# schema.net
KiCad netlist of a schematic drawn in EAGLE
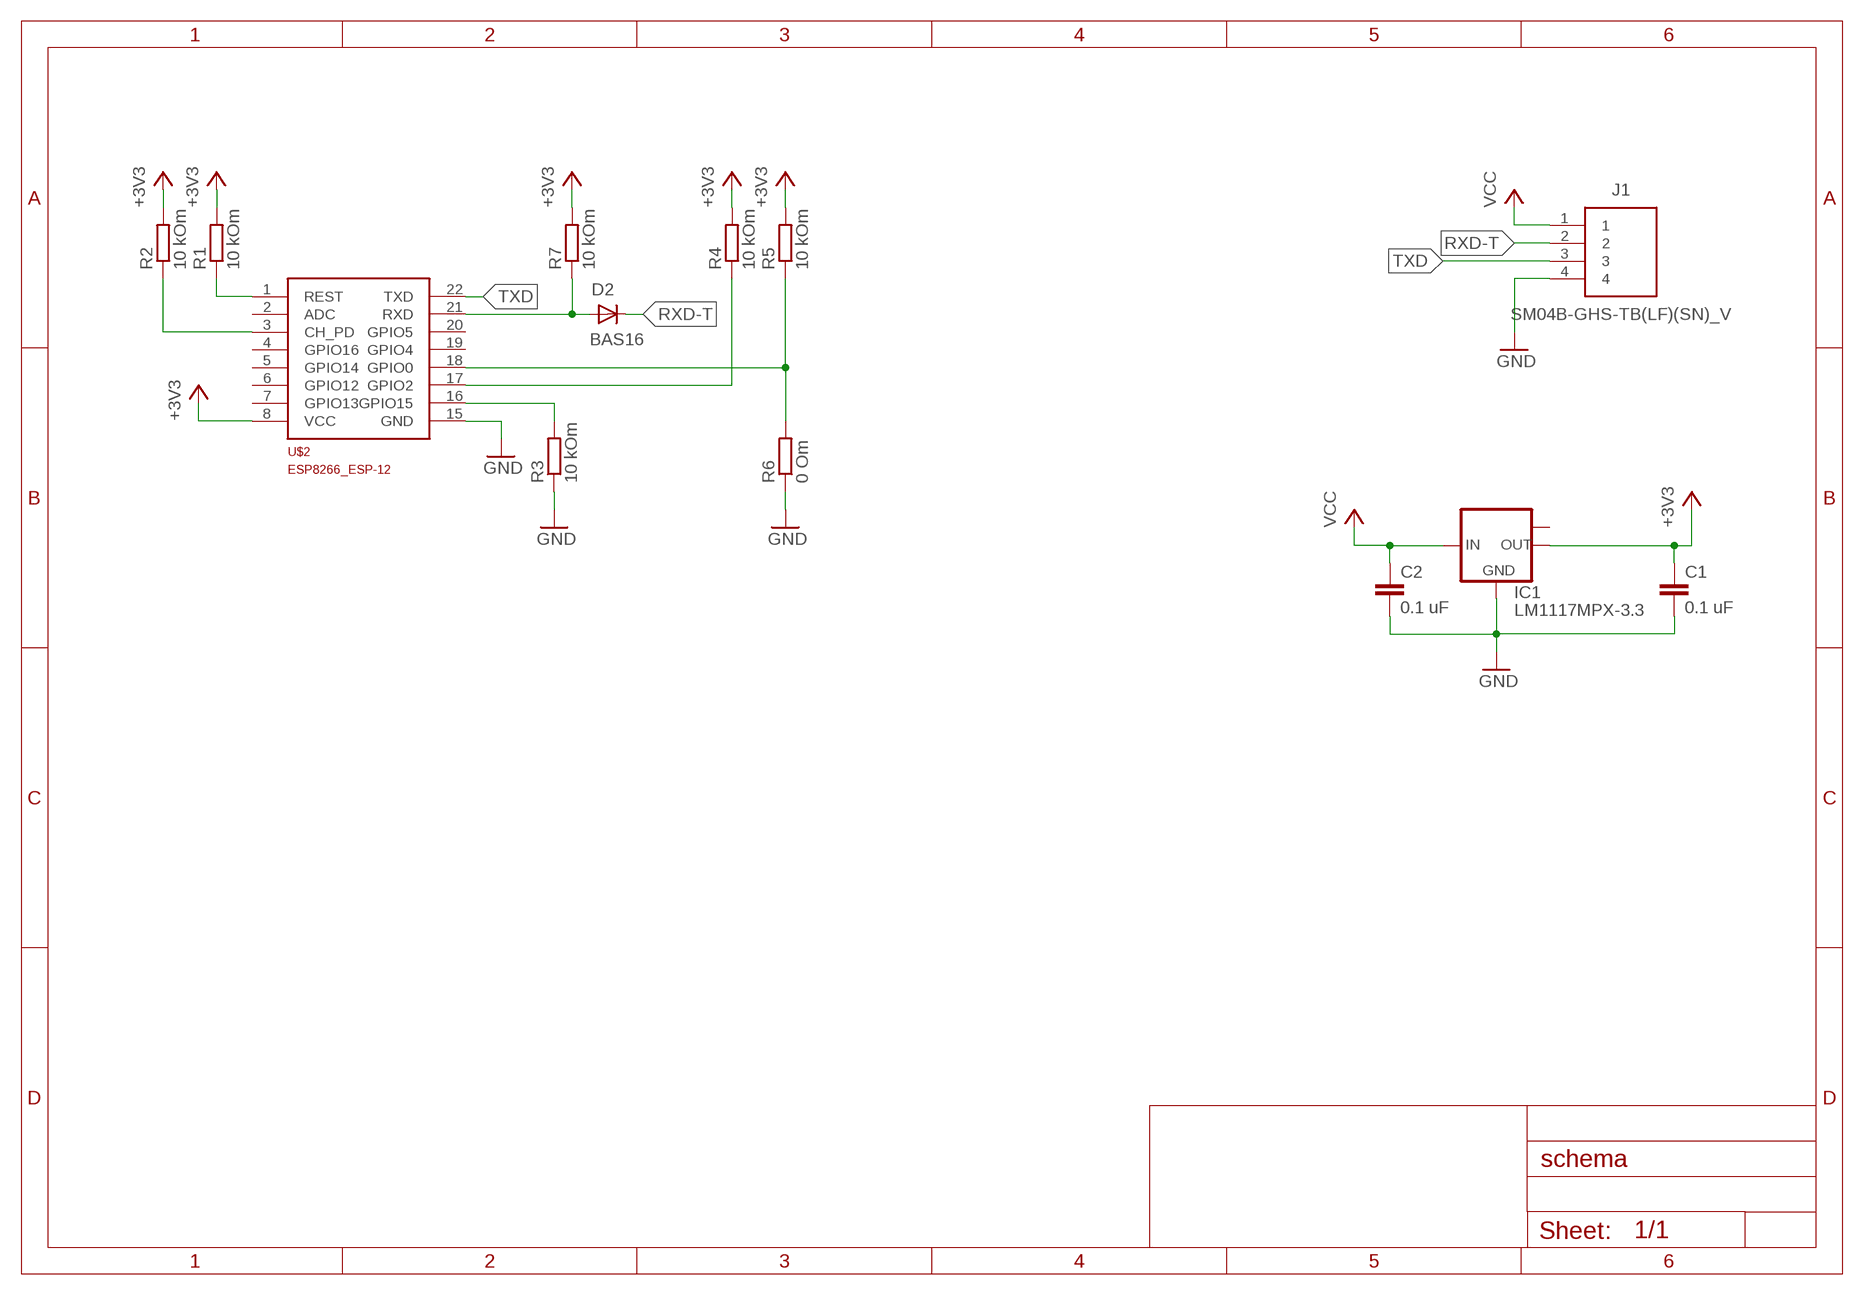
[diagram p0: schematic, sheet 1]

(export (version "E")
  (design (tool "Eeschema 10.0.6"))
  (components
    (comp (ref "C1")
      (value "0.1 uF")
      (footprint "eagle-import:C0603")
      (libsource (lib "eagle-import") (part "C-EUC0603"))
    )
    (comp (ref "C2")
      (value "0.1 uF")
      (footprint "eagle-import:C0603")
      (libsource (lib "eagle-import") (part "C-EUC0603"))
    )
    (comp (ref "D2")
      (value "BAS16")
      (footprint "eagle-import:SOT23")
      (libsource (lib "eagle-import") (part "BAS16"))
    )
    (comp (ref "IC1")
      (value "LM1117MPX-3.3")
      (footprint "eagle-import:SOT223")
      (libsource (lib "eagle-import") (part "LM1117MPX-3.3"))
    )
    (comp (ref "J1")
      (value "SM04B-GHS-TB(LF)(SN)_V")
      (footprint "eagle-import:SM04B-GHS-TB")
      (fields
        (field (name "MANUFACTURER_PART_NUMBER") "SM04B-GHS-TB(LF)(SN)")
        (field (name "RS_PART_NUMBER") "7521797")
      )
      (libsource (lib "eagle-import") (part "SM04B-GHS-TB(LF)(SN)_V"))
    )
    (comp (ref "R1")
      (value "10 kOm")
      (footprint "eagle-import:R0603")
      (libsource (lib "eagle-import") (part "R-EU_R0603"))
    )
    (comp (ref "R2")
      (value "10 kOm")
      (footprint "eagle-import:R0603")
      (libsource (lib "eagle-import") (part "R-EU_R0603"))
    )
    (comp (ref "R3")
      (value "10 kOm")
      (footprint "eagle-import:R0603")
      (libsource (lib "eagle-import") (part "R-EU_R0603"))
    )
    (comp (ref "R4")
      (value "10 kOm")
      (footprint "eagle-import:R0603")
      (libsource (lib "eagle-import") (part "R-EU_R0603"))
    )
    (comp (ref "R5")
      (value "10 kOm")
      (footprint "eagle-import:R0603")
      (libsource (lib "eagle-import") (part "R-EU_R0603"))
    )
    (comp (ref "R6")
      (value "0 Om")
      (footprint "eagle-import:R0603")
      (libsource (lib "eagle-import") (part "R-EU_R0603"))
    )
    (comp (ref "R7")
      (value "10 kOm")
      (footprint "eagle-import:R0603")
      (libsource (lib "eagle-import") (part "R-EU_R0603"))
    )
    (comp (ref "U$2")
      (value "ESP8266_ESP-12F")
      (footprint "eagle-import:ESP8266-ESP12")
      (libsource (lib "eagle-import") (part "ESP8266_ESP-12F"))
    )
  )
  (nets
    (net (code "1") (name "+3V3") (class "Default")
      (node (ref "C1") (pin "1") (pinfunction "1_1") (pintype "passive"))
      (node (ref "IC1") (pin "2") (pinfunction "OUT_2") (pintype "passive"))
      (node (ref "R1") (pin "2") (pinfunction "2_2") (pintype "passive"))
      (node (ref "R2") (pin "2") (pinfunction "2_2") (pintype "passive"))
      (node (ref "R4") (pin "2") (pinfunction "2_2") (pintype "passive"))
      (node (ref "R5") (pin "2") (pinfunction "2_2") (pintype "passive"))
      (node (ref "R7") (pin "2") (pinfunction "2_2") (pintype "passive"))
      (node (ref "U$2") (pin "8") (pinfunction "VCC_8") (pintype "bidirectional"))
    )
    (net (code "2") (name "GND") (class "Default")
      (node (ref "C1") (pin "2") (pinfunction "2_2") (pintype "passive"))
      (node (ref "C2") (pin "2") (pinfunction "2_2") (pintype "passive"))
      (node (ref "IC1") (pin "1") (pinfunction "GND_1") (pintype "input"))
      (node (ref "J1") (pin "4") (pinfunction "4_4") (pintype "passive"))
      (node (ref "R3") (pin "1") (pinfunction "1_1") (pintype "passive"))
      (node (ref "R6") (pin "1") (pinfunction "1_1") (pintype "passive"))
      (node (ref "U$2") (pin "15") (pinfunction "GND_15") (pintype "bidirectional"))
    )
    (net (code "3") (name "Net-(D2-A)") (class "Default")
      (node (ref "D2") (pin "1") (pinfunction "A_1") (pintype "passive"))
      (node (ref "R7") (pin "1") (pinfunction "1_1") (pintype "passive"))
      (node (ref "U$2") (pin "21") (pinfunction "RXD_21") (pintype "bidirectional"))
    )
    (net (code "4") (name "Net-(U$2-CH_PD)") (class "Default")
      (node (ref "R2") (pin "1") (pinfunction "1_1") (pintype "passive"))
      (node (ref "U$2") (pin "3") (pinfunction "CH_PD_3") (pintype "bidirectional"))
    )
    (net (code "5") (name "Net-(U$2-GPIO0)") (class "Default")
      (node (ref "R5") (pin "1") (pinfunction "1_1") (pintype "passive"))
      (node (ref "R6") (pin "2") (pinfunction "2_2") (pintype "passive"))
      (node (ref "U$2") (pin "18") (pinfunction "GPIO0_18") (pintype "bidirectional"))
    )
    (net (code "6") (name "Net-(U$2-GPIO2)") (class "Default")
      (node (ref "R4") (pin "1") (pinfunction "1_1") (pintype "passive"))
      (node (ref "U$2") (pin "17") (pinfunction "GPIO2_17") (pintype "bidirectional"))
    )
    (net (code "7") (name "Net-(U$2-GPIO15)") (class "Default")
      (node (ref "R3") (pin "2") (pinfunction "2_2") (pintype "passive"))
      (node (ref "U$2") (pin "16") (pinfunction "GPIO15_16") (pintype "bidirectional"))
    )
    (net (code "8") (name "Net-(U$2-REST)") (class "Default")
      (node (ref "R1") (pin "1") (pinfunction "1_1") (pintype "passive"))
      (node (ref "U$2") (pin "1") (pinfunction "REST_1") (pintype "bidirectional"))
    )
    (net (code "9") (name "RXD-T") (class "Default")
      (node (ref "D2") (pin "3") (pinfunction "K_3") (pintype "passive"))
      (node (ref "J1") (pin "2") (pinfunction "2_2") (pintype "passive"))
    )
    (net (code "10") (name "TXD") (class "Default")
      (node (ref "J1") (pin "3") (pinfunction "3_3") (pintype "passive"))
      (node (ref "U$2") (pin "22") (pinfunction "TXD_22") (pintype "bidirectional"))
    )
    (net (code "11") (name "VCC") (class "Default")
      (node (ref "C2") (pin "1") (pinfunction "1_1") (pintype "passive"))
      (node (ref "IC1") (pin "3") (pinfunction "IN_3") (pintype "input"))
      (node (ref "J1") (pin "1") (pinfunction "1_1") (pintype "passive"))
    )
    (net (code "12") (name "unconnected-(IC1-OUT1-PadTAB)") (class "Default")
      (node (ref "IC1") (pin "TAB") (pinfunction "OUT1_TAB") (pintype "passive"))
    )
    (net (code "13") (name "unconnected-(U$2-ADC-Pad2)") (class "Default")
      (node (ref "U$2") (pin "2") (pinfunction "ADC_2") (pintype "bidirectional"))
    )
    (net (code "14") (name "unconnected-(U$2-GPIO4-Pad19)") (class "Default")
      (node (ref "U$2") (pin "19") (pinfunction "GPIO4_19") (pintype "bidirectional"))
    )
    (net (code "15") (name "unconnected-(U$2-GPIO5-Pad20)") (class "Default")
      (node (ref "U$2") (pin "20") (pinfunction "GPIO5_20") (pintype "bidirectional"))
    )
    (net (code "16") (name "unconnected-(U$2-GPIO12-Pad6)") (class "Default")
      (node (ref "U$2") (pin "6") (pinfunction "GPIO12_6") (pintype "bidirectional"))
    )
    (net (code "17") (name "unconnected-(U$2-GPIO13-Pad7)") (class "Default")
      (node (ref "U$2") (pin "7") (pinfunction "GPIO13_7") (pintype "bidirectional"))
    )
    (net (code "18") (name "unconnected-(U$2-GPIO14-Pad5)") (class "Default")
      (node (ref "U$2") (pin "5") (pinfunction "GPIO14_5") (pintype "bidirectional"))
    )
    (net (code "19") (name "unconnected-(U$2-GPIO16-Pad4)") (class "Default")
      (node (ref "U$2") (pin "4") (pinfunction "GPIO16_4") (pintype "bidirectional"))
    )
  )
)
